# Power.net
KiCad netlist of a schematic drawn in Altium Designer
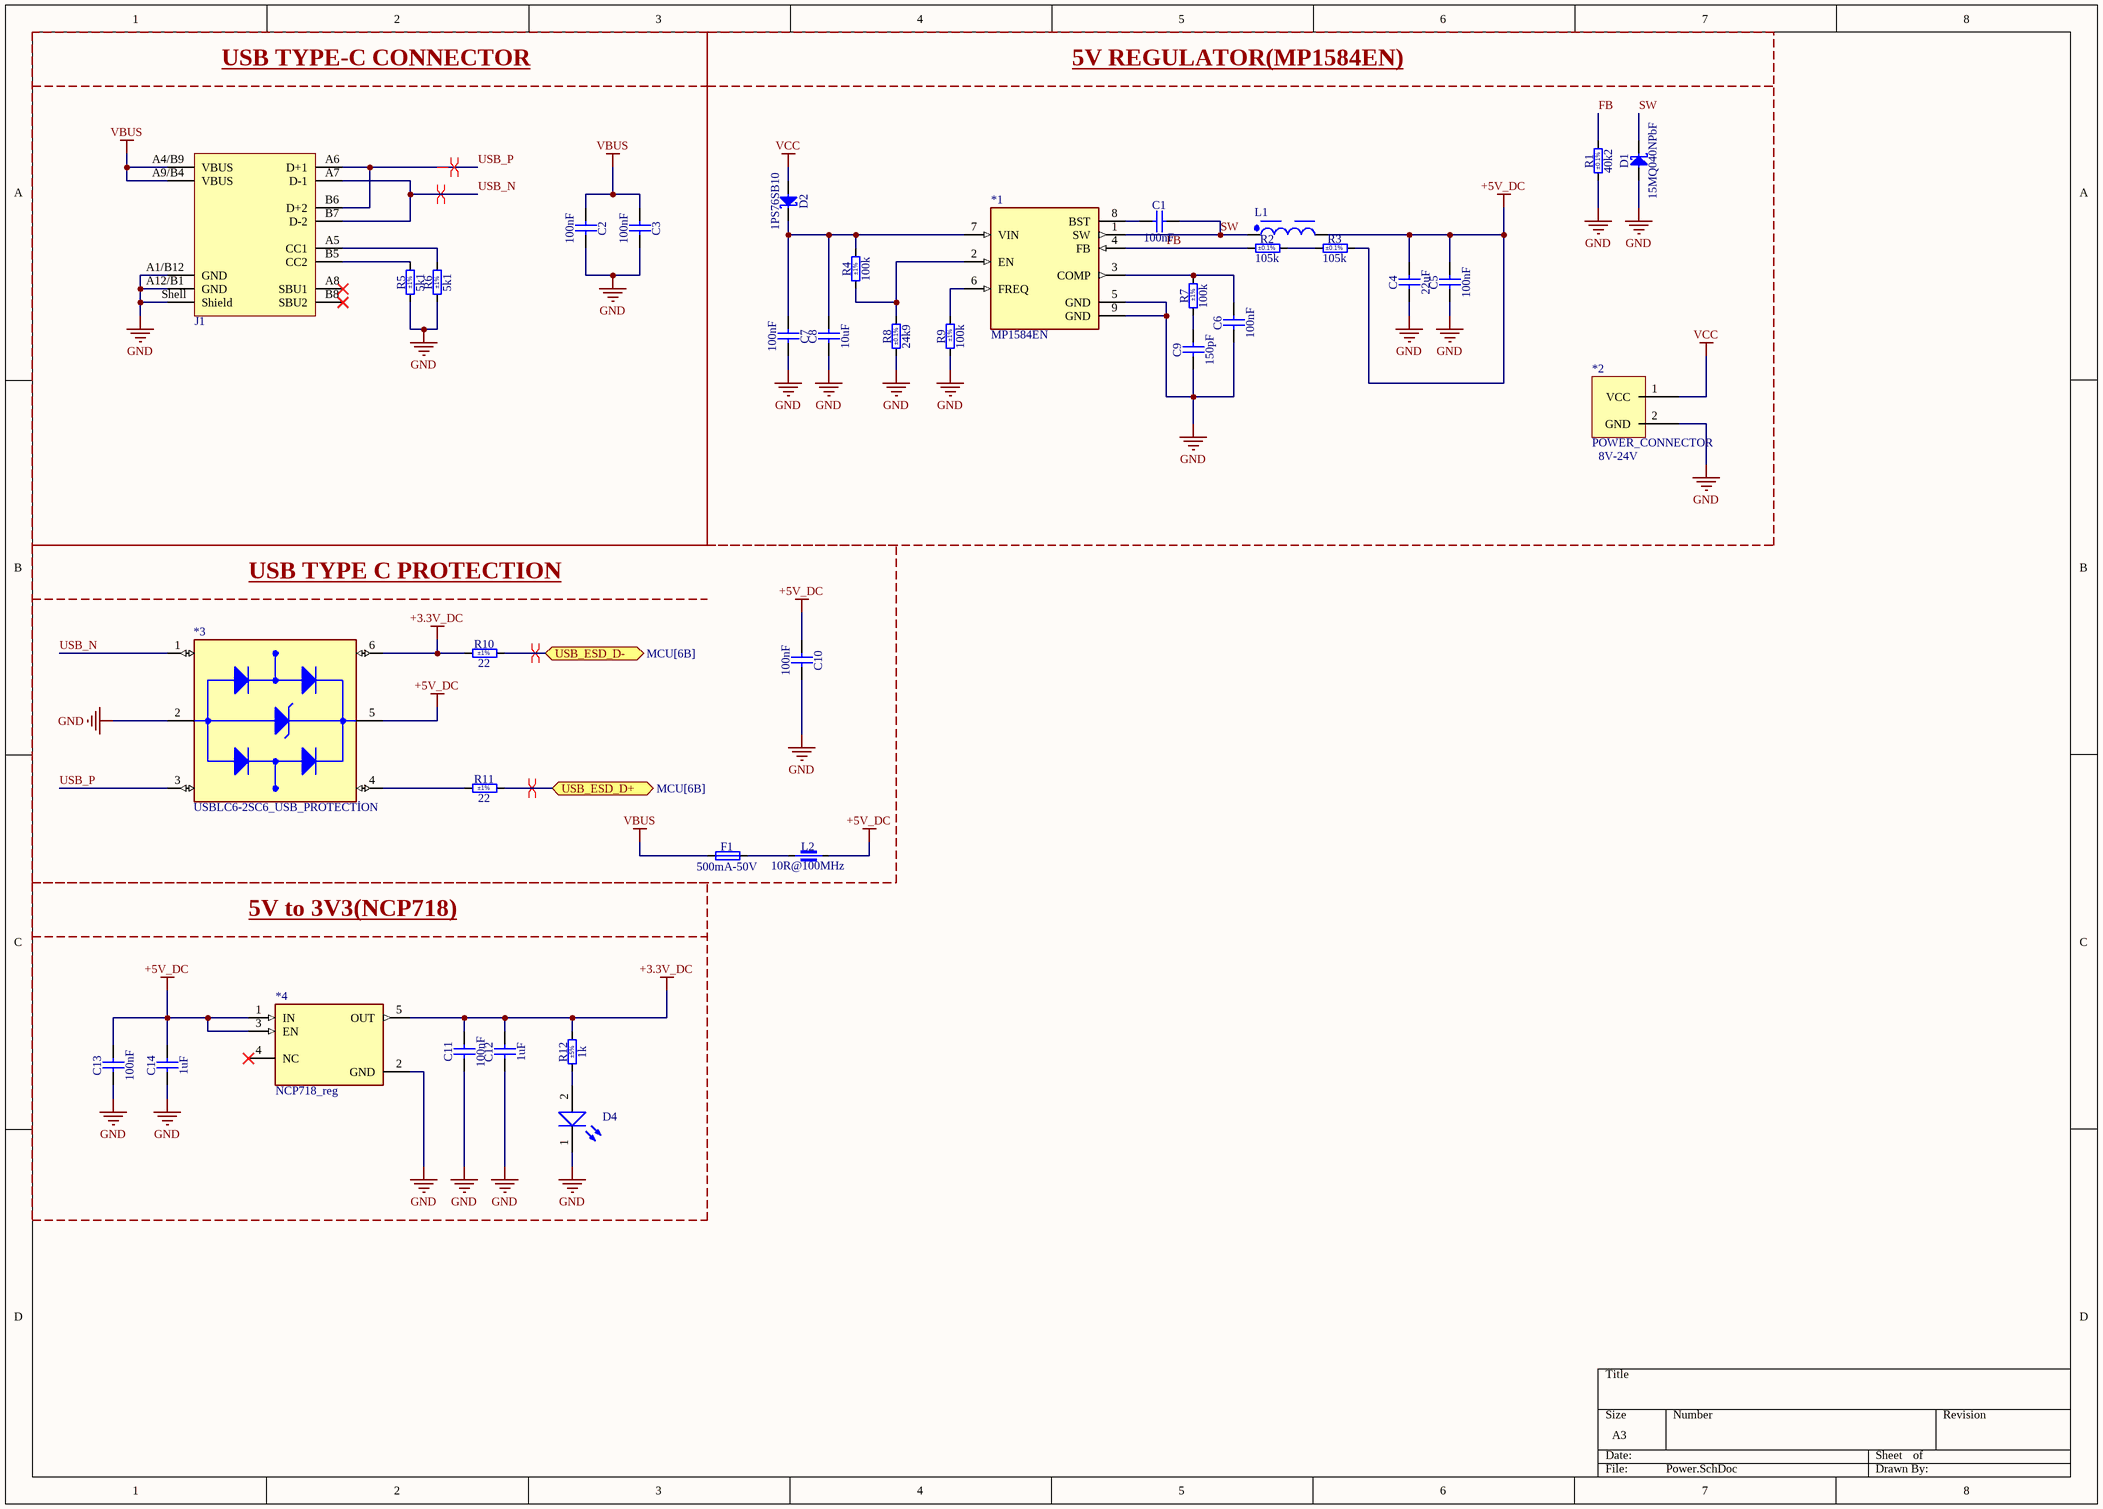
[diagram p0: Power.SchDoc]

(export (version "E")
  (design (tool "Eeschema 10.0.6"))
  (components
    (comp (ref "*1")
      (value "MP1584EN")
      (footprint "MP1584EN")
      (libsource (lib "UDEMY_Library") (part "MP1584EN"))
    )
    (comp (ref "*2")
      (value "POWER_CONNECTOR")
      (footprint "POWER_CONNECTOR_lion_batt")
      (libsource (lib "UDEMY_Library") (part "POWER_CONNECTOR_lion_batt"))
    )
    (comp (ref "*3")
      (value "USBLC6-2SC6_USB_PROTECTİON")
      (footprint "USBLC6-2SC6_USB_PROTECTION")
      (libsource (lib "UDEMY_Library") (part "USBLC6-2SC6_USB_PROTECTİON"))
    )
    (comp (ref "*4")
      (value "NCP718_reg")
      (footprint "NCP718_reg")
      (libsource (lib "UDEMY_Library") (part "NCP718_reg"))
    )
    (comp (ref "C1")
      (value "100nF")
      (footprint "CAPC2012X135N")
      (description "Non-polarised capacitor")
      (fields
        (field (name "PART NUMBER") "CC0805_100NF_50V_10%_X7R")
        (field (name "VOLTAGE") "50V")
        (field (name "AUTHOR") "CERN DEM JLC")
      )
      (libsource (lib "Capacitors") (part "Capacitor - non polarized"))
    )
    (comp (ref "C2")
      (value "100nF")
      (footprint "CAPC2012X135N")
      (description "Non-polarised capacitor")
      (fields
        (field (name "PART NUMBER") "CC0805_100NF_50V_10%_X7R")
        (field (name "VOLTAGE") "50V")
        (field (name "AUTHOR") "CERN DEM JLC")
      )
      (libsource (lib "Capacitors") (part "Capacitor - non polarized"))
    )
    (comp (ref "C3")
      (value "100nF")
      (footprint "CAPC2012X135N")
      (description "Non-polarised capacitor")
      (fields
        (field (name "PART NUMBER") "CC0805_100NF_50V_10%_X7R")
        (field (name "VOLTAGE") "50V")
        (field (name "AUTHOR") "CERN DEM JLC")
      )
      (libsource (lib "Capacitors") (part "Capacitor - non polarized"))
    )
    (comp (ref "C4")
      (value "22uF")
      (footprint "CAPC2012X135N")
      (description "Non-polarised capacitor")
      (fields
        (field (name "PART NUMBER") "CC0805_22UF_16V_10%_X5R")
        (field (name "VOLTAGE") "16V")
        (field (name "AUTHOR") "CERN DEM JLC")
      )
      (libsource (lib "Capacitors") (part "Capacitor - non polarized"))
    )
    (comp (ref "C5")
      (value "100nF")
      (footprint "CAPC2012X135N")
      (description "Non-polarised capacitor")
      (fields
        (field (name "PART NUMBER") "CC0805_100NF_50V_10%_X7R")
        (field (name "VOLTAGE") "50V")
        (field (name "AUTHOR") "CERN DEM JLC")
      )
      (libsource (lib "Capacitors") (part "Capacitor - non polarized"))
    )
    (comp (ref "C6")
      (value "100nF")
      (footprint "CAPC2012X135N")
      (description "Non-polarised capacitor")
      (fields
        (field (name "PART NUMBER") "CC0805_100NF_50V_10%_X7R")
        (field (name "VOLTAGE") "50V")
        (field (name "AUTHOR") "CERN DEM JLC")
      )
      (libsource (lib "Capacitors") (part "Capacitor - non polarized"))
    )
    (comp (ref "C7")
      (value "100nF")
      (footprint "CAPC2012X135N")
      (description "Non-polarised capacitor")
      (fields
        (field (name "PART NUMBER") "CC0805_100NF_50V_10%_X7R")
        (field (name "VOLTAGE") "50V")
        (field (name "AUTHOR") "CERN DEM JLC")
      )
      (libsource (lib "Capacitors") (part "Capacitor - non polarized"))
    )
    (comp (ref "C8")
      (value "10uF")
      (footprint "CAPC2012X145N")
      (description "Non-polarised capacitor")
      (fields
        (field (name "PART NUMBER") "CC0805_10UF_25V_10%_X5R_YUDEN_TMK212BBJ106KGHT")
        (field (name "VOLTAGE") "25V")
        (field (name "AUTHOR") "CERN DEM JLC")
      )
      (libsource (lib "Capacitors") (part "Capacitor - non polarized"))
    )
    (comp (ref "C9")
      (value "150pF")
      (footprint "CAPC2012X135N")
      (description "Non-polarised capacitor")
      (fields
        (field (name "PART NUMBER") "CC0805_150PF_50V_5%_C0G")
        (field (name "VOLTAGE") "50V")
        (field (name "AUTHOR") "CERN DEM JLC")
      )
      (libsource (lib "Capacitors") (part "Capacitor - non polarized"))
    )
    (comp (ref "C10")
      (value "100nF")
      (footprint "CAPC2012X135N")
      (description "Non-polarised capacitor")
      (fields
        (field (name "PART NUMBER") "CC0805_100NF_50V_10%_X7R")
        (field (name "VOLTAGE") "50V")
        (field (name "AUTHOR") "CERN DEM JLC")
      )
      (libsource (lib "Capacitors") (part "Capacitor - non polarized"))
    )
    (comp (ref "C11")
      (value "100nF")
      (footprint "CAPC2012X135N")
      (description "Non-polarised capacitor")
      (fields
        (field (name "PART NUMBER") "CC0805_100NF_50V_10%_X7R")
        (field (name "VOLTAGE") "50V")
        (field (name "AUTHOR") "CERN DEM JLC")
      )
      (libsource (lib "Capacitors") (part "Capacitor - non polarized"))
    )
    (comp (ref "C12")
      (value "1uF")
      (footprint "CAPC2012X140N")
      (description "Non-polarised capacitor")
      (fields
        (field (name "PART NUMBER") "CC0805_1UF_35V_20%_X7R")
        (field (name "VOLTAGE") "35V")
        (field (name "AUTHOR") "CERN DEM JLC")
      )
      (libsource (lib "Capacitors") (part "Capacitor - non polarized"))
    )
    (comp (ref "C13")
      (value "100nF")
      (footprint "CAPC2012X135N")
      (description "Non-polarised capacitor")
      (fields
        (field (name "PART NUMBER") "CC0805_100NF_50V_10%_X7R")
        (field (name "VOLTAGE") "50V")
        (field (name "AUTHOR") "CERN DEM JLC")
      )
      (libsource (lib "Capacitors") (part "Capacitor - non polarized"))
    )
    (comp (ref "C14")
      (value "1uF")
      (footprint "CAPC2012X140N")
      (description "Non-polarised capacitor")
      (fields
        (field (name "PART NUMBER") "CC0805_1UF_35V_20%_X7R")
        (field (name "VOLTAGE") "35V")
        (field (name "AUTHOR") "CERN DEM JLC")
      )
      (libsource (lib "Capacitors") (part "Capacitor - non polarized"))
    )
    (comp (ref "D1")
      (value "15MQ040NPbF")
      (footprint "DIOM5027X244N")
      (description "Schottky Diode")
      (fields
        (field (name "VOLTAGE") "40V")
        (field (name "POWER") "3A")
        (field (name "AUTHOR") "CERN DEM JLC")
      )
      (libsource (lib "ICs And Semiconductors") (part "Diode Schottky"))
    )
    (comp (ref "D2")
      (value "1PS76SB10")
      (footprint "SOD2512X110N")
      (description "Schottky Diode")
      (fields
        (field (name "VOLTAGE") "30V")
        (field (name "POWER") "200mA")
        (field (name "AUTHOR") "CERN DEM JLC")
      )
      (libsource (lib "ICs And Semiconductors") (part "Diode Schottky"))
    )
    (comp (ref "D4")
      (value "Sunrise, 3V, 120°")
      (footprint "WL-SWTP_3014_L3W1.4H0.8")
      (description "WL-SWTP SMT White Top view PLCC, size 3014, Sunrise, 3V, 120°")
      (fields
        (field (name "MANUFACTURER PART NUMBER") "158301227")
        (field (name "MANUFACTURER") "Wurth Elektronik")
      )
      (libsource (lib "WE - Optoelectronic Components") (part "LED_Transparent_2A-1K"))
    )
    (comp (ref "F1")
      (value "500mA-50V")
      (footprint "FUSC_BOURNS_SF-0603F")
      (description "Fuse")
      (fields
        (field (name "PART NUMBER") "FUS0603_BOURNS-SF-0603F050-2")
        (field (name "MANUFACTURER") "BOURNS")
        (field (name "AUTHOR") "CERN DEM JLC")
      )
      (libsource (lib "Eletro-mechanical") (part "Fuse"))
    )
    (comp (ref "J1")
      (value "629722000214")
      (footprint "629722000214")
      (description "WR-COM USB 2.0 Type C Receptacle Horizontal SMT")
      (fields (field (name "MANUFACTURER") "Wurth Elektronik"))
      (libsource (lib "WE - Electromechanical Components") (part "USB 2.0_Type C_Receptacle_1 Port_629722000214"))
    )
    (comp (ref "L1")
      (value "15uH, 4.2A")
      (footprint "WE-PD_1260")
      (description "WE-PD SMT Power Inductor, size 1260, 15uH, 4.2A, 28mOhm")
      (fields
        (field (name "MANUFACTURER PART NUMBER") "744771115")
        (field (name "MANUFACTURER") "Wurth Elektronik")
      )
      (libsource (lib "WE - Passive Components") (part "Inductor - 2"))
    )
    (comp (ref "L2")
      (value "10R@100MHz")
      (footprint "INDC1608X95N")
      (fields
        (field (name "PART NUMBER") "IND0603_MURATA_BLM18BA100SN1D")
        (field (name "POWER") "500mA")
        (field (name "TOLERANCE") "±25%")
        (field (name "AUTHOR") "CERN DEM JLC")
      )
      (libsource (lib "Inductors & Transformers") (part "Ferrite Bead"))
    )
    (comp (ref "R1")
      (value "40k2")
      (footprint "RESC2012X60N")
      (description "Resistor - 0.1%")
      (fields
        (field (name "TOLERANCE") "±0.1%")
        (field (name "PART NUMBER") "R0805_40K2_0.1%_0.125W_15PPM")
        (field (name "POWER") "0.125W")
        (field (name "AUTHOR") "CERN DEM JLC")
      )
      (libsource (lib "Resistors") (part "Resistor - 0.1%"))
    )
    (comp (ref "R2")
      (value "105k")
      (footprint "RESC2012X60N")
      (description "Resistor - 0.1%")
      (fields
        (field (name "TOLERANCE") "±0.1%")
        (field (name "PART NUMBER") "R0805_105K_0.1%_0.1W_10PPM")
        (field (name "POWER") "0.1W")
        (field (name "AUTHOR") "CERN DEM JLC")
      )
      (libsource (lib "Resistors") (part "Resistor - 0.1%"))
    )
    (comp (ref "R3")
      (value "105k")
      (footprint "RESC2012X60N")
      (description "Resistor - 0.1%")
      (fields
        (field (name "TOLERANCE") "±0.1%")
        (field (name "PART NUMBER") "R0805_105K_0.1%_0.1W_10PPM")
        (field (name "POWER") "0.1W")
        (field (name "AUTHOR") "CERN DEM JLC")
      )
      (libsource (lib "Resistors") (part "Resistor - 0.1%"))
    )
    (comp (ref "R4")
      (value "100k")
      (footprint "RESC2012X60N")
      (description "Resistor - 1%")
      (fields
        (field (name "TOLERANCE") "±1%")
        (field (name "PART NUMBER") "R0805_100K_1%_0.125W_100PPM")
        (field (name "POWER") "0.125W")
        (field (name "AUTHOR") "CERN DEM JLC")
      )
      (libsource (lib "Resistors") (part "Resistor - 1%"))
    )
    (comp (ref "R5")
      (value "5k1")
      (footprint "RESC2012X60N")
      (description "Resistor - 1%")
      (fields
        (field (name "TOLERANCE") "±1%")
        (field (name "PART NUMBER") "R0805_5K1_1%_0.125W_100PPM")
        (field (name "POWER") "0.125W")
        (field (name "AUTHOR") "CERN DEM JLC")
      )
      (libsource (lib "Resistors") (part "Resistor - 1%"))
    )
    (comp (ref "R6")
      (value "5k1")
      (footprint "RESC2012X60N")
      (description "Resistor - 1%")
      (fields
        (field (name "TOLERANCE") "±1%")
        (field (name "PART NUMBER") "R0805_5K1_1%_0.125W_100PPM")
        (field (name "POWER") "0.125W")
        (field (name "AUTHOR") "CERN DEM JLC")
      )
      (libsource (lib "Resistors") (part "Resistor - 1%"))
    )
    (comp (ref "R7")
      (value "100k")
      (footprint "RESC2012X60N")
      (description "Resistor - 1%")
      (fields
        (field (name "TOLERANCE") "±1%")
        (field (name "PART NUMBER") "R0805_100K_1%_0.125W_100PPM")
        (field (name "POWER") "0.125W")
        (field (name "AUTHOR") "CERN DEM JLC")
      )
      (libsource (lib "Resistors") (part "Resistor - 1%"))
    )
    (comp (ref "R8")
      (value "24k9")
      (footprint "RESC2012X60N")
      (description "Resistor - 0.1%")
      (fields
        (field (name "TOLERANCE") "±0.1%")
        (field (name "PART NUMBER") "R0805_24K9_0.1%_0.1W_10PPM")
        (field (name "POWER") "0.1W")
        (field (name "AUTHOR") "CERN DEM JLC")
      )
      (libsource (lib "Resistors") (part "Resistor - 0.1%"))
    )
    (comp (ref "R9")
      (value "100k")
      (footprint "RESC2012X60N")
      (description "Resistor - 1%")
      (fields
        (field (name "TOLERANCE") "±1%")
        (field (name "PART NUMBER") "R0805_100K_1%_0.125W_100PPM")
        (field (name "POWER") "0.125W")
        (field (name "AUTHOR") "CERN DEM JLC")
      )
      (libsource (lib "Resistors") (part "Resistor - 1%"))
    )
    (comp (ref "R10")
      (value "22")
      (footprint "RESC2012X60N")
      (description "Resistor - 1%")
      (fields
        (field (name "TOLERANCE") "±1%")
        (field (name "PART NUMBER") "R0805_22R_1%_0.125W_100PPM")
        (field (name "POWER") "0.125W")
        (field (name "AUTHOR") "CERN DEM JLC")
      )
      (libsource (lib "Resistors") (part "Resistor - 1%"))
    )
    (comp (ref "R11")
      (value "22")
      (footprint "RESC2012X60N")
      (description "Resistor - 1%")
      (fields
        (field (name "TOLERANCE") "±1%")
        (field (name "PART NUMBER") "R0805_22R_1%_0.125W_100PPM")
        (field (name "POWER") "0.125W")
        (field (name "AUTHOR") "CERN DEM JLC")
      )
      (libsource (lib "Resistors") (part "Resistor - 1%"))
    )
    (comp (ref "R12")
      (value "1k")
      (footprint "RESC2012X60N")
      (description "Resistor - 0.1%")
      (fields
        (field (name "TOLERANCE") "±5%")
        (field (name "PART NUMBER") "R0805_1K_0.1%_0.125W_25PPM")
        (field (name "POWER") "0.125W")
        (field (name "AUTHOR") "CERN DEM JLC")
      )
      (libsource (lib "Resistors") (part "Resistor - 0.1%"))
    )
  )
  (nets
    (net (code "1") (name "+3.3V_DC") (class "Default")
      (node (ref "*3") (pin "6") (pinfunction "I/O1_OUT_6") (pintype "bidirectional"))
      (node (ref "*4") (pin "5") (pinfunction "OUT_5") (pintype "output"))
      (node (ref "C11") (pin "2") (pinfunction "2_2") (pintype "passive"))
      (node (ref "C12") (pin "2") (pinfunction "2_2") (pintype "passive"))
      (node (ref "R10") (pin "1") (pinfunction "1_1") (pintype "passive"))
      (node (ref "R12") (pin "2") (pinfunction "2_2") (pintype "passive"))
    )
    (net (code "2") (name "+5V_DC") (class "Default")
      (node (ref "*3") (pin "5") (pinfunction "VBUS_5") (pintype "power_in"))
      (node (ref "*4") (pin "1") (pinfunction "IN_1") (pintype "input"))
      (node (ref "*4") (pin "3") (pinfunction "EN_3") (pintype "input"))
      (node (ref "C10") (pin "1") (pinfunction "1_1") (pintype "passive"))
      (node (ref "C13") (pin "2") (pinfunction "2_2") (pintype "passive"))
      (node (ref "C14") (pin "2") (pinfunction "2_2") (pintype "passive"))
      (node (ref "C4") (pin "2") (pinfunction "2_2") (pintype "passive"))
      (node (ref "C5") (pin "2") (pinfunction "2_2") (pintype "passive"))
      (node (ref "L1") (pin "2") (pinfunction "2_2") (pintype "passive"))
      (node (ref "L2") (pin "2") (pinfunction "2_2") (pintype "passive"))
      (node (ref "R3") (pin "2") (pinfunction "2_2") (pintype "passive"))
    )
    (net (code "3") (name "/FB") (class "Default")
      (node (ref "*1") (pin "4") (pinfunction "FB_4") (pintype "input"))
      (node (ref "R1") (pin "2") (pinfunction "2_2") (pintype "passive"))
      (node (ref "R2") (pin "1") (pinfunction "1_1") (pintype "passive"))
    )
    (net (code "4") (name "/SW") (class "Default")
      (node (ref "*1") (pin "1") (pinfunction "SW_1") (pintype "output"))
      (node (ref "C1") (pin "2") (pinfunction "2_2") (pintype "passive"))
      (node (ref "D1") (pin "1") (pinfunction "C_1") (pintype "passive"))
      (node (ref "L1") (pin "1") (pinfunction "1_1") (pintype "passive"))
    )
    (net (code "5") (name "/USB_ESD_D+") (class "Default")
      (node (ref "R11") (pin "2") (pinfunction "2_2") (pintype "passive"))
    )
    (net (code "6") (name "/USB_ESD_D-") (class "Default")
      (node (ref "R10") (pin "2") (pinfunction "2_2") (pintype "passive"))
    )
    (net (code "7") (name "/USB_N") (class "Default")
      (node (ref "*3") (pin "1") (pinfunction "I/O1_IN_1") (pintype "bidirectional"))
      (node (ref "J1") (pin "A7") (pinfunction "D-1_A7") (pintype "passive"))
      (node (ref "J1") (pin "B7") (pinfunction "D-2_B7") (pintype "passive"))
    )
    (net (code "8") (name "/USB_P") (class "Default")
      (node (ref "*3") (pin "3") (pinfunction "I/O2_IN_3") (pintype "bidirectional"))
      (node (ref "J1") (pin "A6") (pinfunction "D+1_A6") (pintype "passive"))
      (node (ref "J1") (pin "B6") (pinfunction "D+2_B6") (pintype "passive"))
    )
    (net (code "9") (name "GND") (class "Default")
      (node (ref "*1") (pin "5") (pinfunction "GND_5") (pintype "power_in"))
      (node (ref "*1") (pin "9") (pinfunction "GND_9") (pintype "power_in"))
      (node (ref "*2") (pin "2") (pinfunction "GND_2") (pintype "passive"))
      (node (ref "*3") (pin "2") (pinfunction "GND_2") (pintype "power_in"))
      (node (ref "*4") (pin "2") (pinfunction "GND_2") (pintype "power_in"))
      (node (ref "C10") (pin "2") (pinfunction "2_2") (pintype "passive"))
      (node (ref "C11") (pin "1") (pinfunction "1_1") (pintype "passive"))
      (node (ref "C12") (pin "1") (pinfunction "1_1") (pintype "passive"))
      (node (ref "C13") (pin "1") (pinfunction "1_1") (pintype "passive"))
      (node (ref "C14") (pin "1") (pinfunction "1_1") (pintype "passive"))
      (node (ref "C2") (pin "2") (pinfunction "2_2") (pintype "passive"))
      (node (ref "C3") (pin "2") (pinfunction "2_2") (pintype "passive"))
      (node (ref "C4") (pin "1") (pinfunction "1_1") (pintype "passive"))
      (node (ref "C5") (pin "1") (pinfunction "1_1") (pintype "passive"))
      (node (ref "C6") (pin "1") (pinfunction "1_1") (pintype "passive"))
      (node (ref "C7") (pin "2") (pinfunction "2_2") (pintype "passive"))
      (node (ref "C8") (pin "1") (pinfunction "1_1") (pintype "passive"))
      (node (ref "C9") (pin "1") (pinfunction "1_1") (pintype "passive"))
      (node (ref "D1") (pin "2") (pinfunction "A_2") (pintype "passive"))
      (node (ref "D4") (pin "1") (pinfunction "K_1") (pintype "passive"))
      (node (ref "J1") (pin "A1/B12") (pinfunction "GND_A1/B12") (pintype "passive"))
      (node (ref "J1") (pin "A12/B1") (pinfunction "GND_A12/B1") (pintype "passive"))
      (node (ref "J1") (pin "Shell") (pinfunction "Shield_Shell") (pintype "passive"))
      (node (ref "R1") (pin "1") (pinfunction "1_1") (pintype "passive"))
      (node (ref "R5") (pin "1") (pinfunction "1_1") (pintype "passive"))
      (node (ref "R6") (pin "1") (pinfunction "1_1") (pintype "passive"))
      (node (ref "R8") (pin "1") (pinfunction "1_1") (pintype "passive"))
      (node (ref "R9") (pin "1") (pinfunction "1_1") (pintype "passive"))
    )
    (net (code "10") (name "Net-(*1-BST)") (class "Default")
      (node (ref "*1") (pin "8") (pinfunction "BST_8") (pintype "passive"))
      (node (ref "C1") (pin "1") (pinfunction "1_1") (pintype "passive"))
    )
    (net (code "11") (name "Net-(*1-COMP)") (class "Default")
      (node (ref "*1") (pin "3") (pinfunction "COMP_3") (pintype "output"))
      (node (ref "C6") (pin "2") (pinfunction "2_2") (pintype "passive"))
      (node (ref "R7") (pin "2") (pinfunction "2_2") (pintype "passive"))
    )
    (net (code "12") (name "Net-(*1-EN)") (class "Default")
      (node (ref "*1") (pin "2") (pinfunction "EN_2") (pintype "input"))
      (node (ref "R4") (pin "1") (pinfunction "1_1") (pintype "passive"))
      (node (ref "R8") (pin "2") (pinfunction "2_2") (pintype "passive"))
    )
    (net (code "13") (name "Net-(*1-FREQ)") (class "Default")
      (node (ref "*1") (pin "6") (pinfunction "FREQ_6") (pintype "input"))
      (node (ref "R9") (pin "2") (pinfunction "2_2") (pintype "passive"))
    )
    (net (code "14") (name "Net-(*1-VIN)") (class "Default")
      (node (ref "*1") (pin "7") (pinfunction "VIN_7") (pintype "input"))
      (node (ref "C7") (pin "1") (pinfunction "1_1") (pintype "passive"))
      (node (ref "C8") (pin "2") (pinfunction "2_2") (pintype "passive"))
      (node (ref "D2") (pin "1") (pinfunction "C_1") (pintype "passive"))
      (node (ref "R4") (pin "2") (pinfunction "2_2") (pintype "passive"))
    )
    (net (code "15") (name "Net-(*3-I{slash}O2_OUT)") (class "Default")
      (node (ref "*3") (pin "4") (pinfunction "I/O2_OUT_4") (pintype "bidirectional"))
      (node (ref "R11") (pin "1") (pinfunction "1_1") (pintype "passive"))
    )
    (net (code "16") (name "Net-(C9-Pad2)") (class "Default")
      (node (ref "C9") (pin "2") (pinfunction "2_2") (pintype "passive"))
      (node (ref "R7") (pin "1") (pinfunction "1_1") (pintype "passive"))
    )
    (net (code "17") (name "Net-(D4-A)") (class "Default")
      (node (ref "D4") (pin "2") (pinfunction "A_2") (pintype "passive"))
      (node (ref "R12") (pin "1") (pinfunction "1_1") (pintype "passive"))
    )
    (net (code "18") (name "Net-(F1-Pad2)") (class "Default")
      (node (ref "F1") (pin "2") (pinfunction "2_2") (pintype "passive"))
      (node (ref "L2") (pin "1") (pinfunction "1_1") (pintype "passive"))
    )
    (net (code "19") (name "Net-(J1-CC1)") (class "Default")
      (node (ref "J1") (pin "A5") (pinfunction "CC1_A5") (pintype "passive"))
      (node (ref "R6") (pin "2") (pinfunction "2_2") (pintype "passive"))
    )
    (net (code "20") (name "Net-(J1-CC2)") (class "Default")
      (node (ref "J1") (pin "B5") (pinfunction "CC2_B5") (pintype "passive"))
      (node (ref "R5") (pin "2") (pinfunction "2_2") (pintype "passive"))
    )
    (net (code "21") (name "Net-(R2-Pad2)") (class "Default")
      (node (ref "R2") (pin "2") (pinfunction "2_2") (pintype "passive"))
      (node (ref "R3") (pin "1") (pinfunction "1_1") (pintype "passive"))
    )
    (net (code "22") (name "VBUS") (class "Default")
      (node (ref "C2") (pin "1") (pinfunction "1_1") (pintype "passive"))
      (node (ref "C3") (pin "1") (pinfunction "1_1") (pintype "passive"))
      (node (ref "F1") (pin "1") (pinfunction "1_1") (pintype "passive"))
      (node (ref "J1") (pin "A4/B9") (pinfunction "VBUS_A4/B9") (pintype "passive"))
      (node (ref "J1") (pin "A9/B4") (pinfunction "VBUS_A9/B4") (pintype "passive"))
    )
    (net (code "23") (name "VCC") (class "Default")
      (node (ref "*2") (pin "1") (pinfunction "VCC_1") (pintype "passive"))
      (node (ref "D2") (pin "2") (pinfunction "A_2") (pintype "passive"))
    )
    (net (code "24") (name "unconnected-(*4-NC-Pad4)") (class "Default")
      (node (ref "*4") (pin "4") (pinfunction "NC_4") (pintype "passive+no_connect"))
    )
    (net (code "25") (name "unconnected-(J1-SBU1-PadA8)") (class "Default")
      (node (ref "J1") (pin "A8") (pinfunction "SBU1_A8") (pintype "passive+no_connect"))
    )
    (net (code "26") (name "unconnected-(J1-SBU2-PadB8)") (class "Default")
      (node (ref "J1") (pin "B8") (pinfunction "SBU2_B8") (pintype "passive+no_connect"))
    )
  )
)
